# controller.net
KiCad netlist of a schematic drawn in Altium Designer
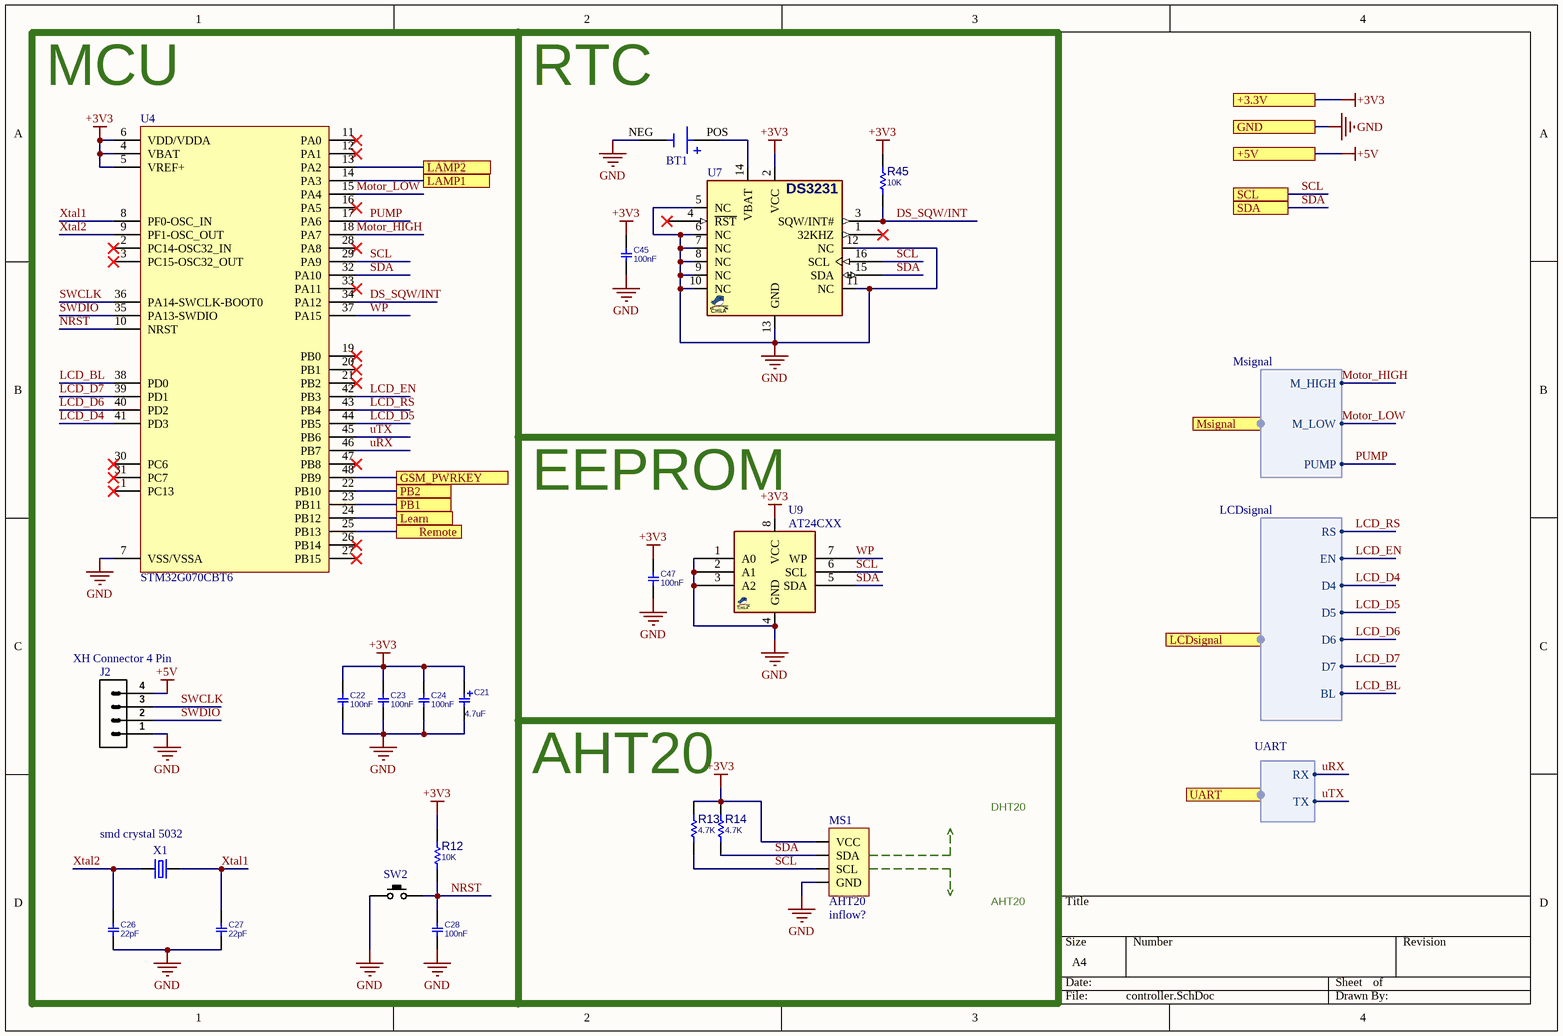
[diagram p0: controller.SchDoc]

(export (version "E")
  (design (tool "Eeschema 10.0.6"))
  (components
    (comp (ref "BT1")
      (value "Coin Cell battery holder")
      (footprint "Coin Cell battery holder")
      (description "2032 Battery")
      (libsource (lib "Mehrdad") (part "Coin Cell battery holder"))
    )
    (comp (ref "C21")
      (value "4.7uF")
      (footprint "C_TN_3216")
      (description "CAP, SMD, TAN,")
      (libsource (lib "passive_smd") (part "CAP_SMD_TAN"))
    )
    (comp (ref "C22")
      (value "100nF")
      (footprint "C0805")
      (description "CAP, MLCC, -F, -V, MATERIAL, -%, 0201")
      (fields (field (name "MANF_P#") "MANF_PART#"))
      (libsource (lib "passive_smd") (part "CAP_SMD_MLCC_0805"))
    )
    (comp (ref "C23")
      (value "100nF")
      (footprint "C0805")
      (description "CAP, MLCC, -F, -V, MATERIAL, -%, 0201")
      (fields (field (name "MANF_P#") "MANF_PART#"))
      (libsource (lib "passive_smd") (part "CAP_SMD_MLCC_0805"))
    )
    (comp (ref "C24")
      (value "100nF")
      (footprint "C0805")
      (description "CAP, MLCC, -F, -V, MATERIAL, -%, 0201")
      (fields (field (name "MANF_P#") "MANF_PART#"))
      (libsource (lib "passive_smd") (part "CAP_SMD_MLCC_0805"))
    )
    (comp (ref "C26")
      (value "22pF")
      (footprint "C0805")
      (description "CAP, MLCC, -F, -V, MATERIAL, -%, 0201")
      (fields (field (name "MANF_P#") "MANF_PART#"))
      (libsource (lib "passive_smd") (part "CAP_SMD_MLCC_0805"))
    )
    (comp (ref "C27")
      (value "22pF")
      (footprint "C0805")
      (description "CAP, MLCC, -F, -V, MATERIAL, -%, 0201")
      (fields (field (name "MANF_P#") "MANF_PART#"))
      (libsource (lib "passive_smd") (part "CAP_SMD_MLCC_0805"))
    )
    (comp (ref "C28")
      (value "100nF")
      (footprint "C0805")
      (description "CAP, MLCC, -F, -V, MATERIAL, -%, 0201")
      (fields (field (name "MANF_P#") "MANF_PART#"))
      (libsource (lib "passive_smd") (part "CAP_SMD_MLCC_0805"))
    )
    (comp (ref "C45")
      (value "100nF")
      (footprint "C0805")
      (description "CAP, MLCC, -F, -V, MATERIAL, -%, 0201")
      (fields (field (name "MANF_P#") "MANF_PART#"))
      (libsource (lib "passive_smd") (part "CAP_SMD_MLCC_0805"))
    )
    (comp (ref "C47")
      (value "100nF")
      (footprint "C0805")
      (description "CAP, MLCC, -F, -V, MATERIAL, -%, 0201")
      (fields (field (name "MANF_P#") "MANF_PART#"))
      (libsource (lib "passive_smd") (part "CAP_SMD_MLCC_0805"))
    )
    (comp (ref "J2")
      (value "XH Connector 4 Pin")
      (footprint "XH 4 Pin - 2.5mm")
      (description "XH, 4-Pin")
      (fields (field (name "PUBLISHER") "Majid Derhambakhsh"))
      (libsource (lib "mBedLab Altium Library (2024-04-20)") (part "XH 4"))
    )
    (comp (ref "MS1")
      (value "AHT20")
      (footprint "AHT20")
      (description "Air Temperature and Humidity Sensor")
      (fields (field (name "INFLOW") "inflow?") (field (name "VALIDATION") "NT"))
      (libsource (lib "AVR_RCS") (part "ModSen_AHT20"))
    )
    (comp (ref "R12")
      (value "10K")
      (footprint "R0805")
      (description "RESISTOR, SMD")
      (libsource (lib "passive_smd") (part "RES_SMD_0805"))
    )
    (comp (ref "R13")
      (value "4.7K")
      (footprint "R0805")
      (description "RESISTOR, SMD")
      (libsource (lib "passive_smd") (part "RES_SMD_0805"))
    )
    (comp (ref "R14")
      (value "4.7K")
      (footprint "R0805")
      (description "RESISTOR, SMD")
      (libsource (lib "passive_smd") (part "RES_SMD_0805"))
    )
    (comp (ref "R45")
      (value "10K")
      (footprint "R0805")
      (description "RESISTOR, SMD")
      (libsource (lib "passive_smd") (part "RES_SMD_0805"))
    )
    (comp (ref "SW2")
      (value "Tactile Switch")
      (footprint "Tactile Switch")
      (description "3x6x5 mm - 2 Pin")
      (libsource (lib "Mehrdad") (part "Tactile Switch"))
    )
    (comp (ref "U4")
      (value "STM32G070CBT6")
      (footprint "STM32G070CBT6")
      (description "ARMÂ® CortexÂ®-M0+ STM32G0 Microcontroller IC 32-Bit 64MHz 128KB _128K x 8_ FLASH 48-LQFP _7x7_")
      (libsource (lib "Mehrdad") (part "STM32G070CBT6"))
    )
    (comp (ref "U7")
      (value "DS3231")
      (footprint "SO_16_W")
      (description "Real-Time Clock, I2C, +IntCryst")
      (fields (field (name "MANF") "Maxim Integrated") (field (name "MANF_P#") "DS3231SN#"))
      (libsource (lib "rtc") (part "DS3231_SOP16W"))
    )
    (comp (ref "U9")
      (value "AT24CXX")
      (footprint "SO_8")
      (description "EEPROM, I2C,")
      (libsource (lib "memory_eeprom_I2C") (part "EEPROM_I2C_AT24CXX_SOP8"))
    )
    (comp (ref "X1")
      (value "smd crystal 5032")
      (footprint "smd crystal 5032")
      (description "8Mhz - 2Pin - 5032 Package")
      (libsource (lib "Mehrdad") (part "smd crystal 5032"))
    )
  )
  (nets
    (net (code "4") (name "+3V3") (class "Default")
      (node (ref "C21") (pin "1") (pinfunction "1_1") (pintype "passive"))
      (node (ref "C22") (pin "2") (pinfunction "2_2") (pintype "passive"))
      (node (ref "C23") (pin "2") (pinfunction "2_2") (pintype "passive"))
      (node (ref "C24") (pin "2") (pinfunction "2_2") (pintype "passive"))
      (node (ref "C45") (pin "2") (pinfunction "2_2") (pintype "passive"))
      (node (ref "C47") (pin "2") (pinfunction "2_2") (pintype "passive"))
      (node (ref "MS1") (pin "4") (pinfunction "VCC_4") (pintype "passive"))
      (node (ref "R12") (pin "1") (pinfunction "1_1") (pintype "passive"))
      (node (ref "R13") (pin "1") (pinfunction "1_1") (pintype "passive"))
      (node (ref "R14") (pin "1") (pinfunction "1_1") (pintype "passive"))
      (node (ref "R45") (pin "1") (pinfunction "1_1") (pintype "passive"))
      (node (ref "U4") (pin "4") (pinfunction "VBAT_4") (pintype "power_in"))
      (node (ref "U4") (pin "5") (pinfunction "VREF+_5") (pintype "power_in"))
      (node (ref "U4") (pin "6") (pinfunction "VDD/VDDA_6") (pintype "power_in"))
      (node (ref "U7") (pin "2") (pinfunction "VCC_2") (pintype "power_in"))
      (node (ref "U9") (pin "8") (pinfunction "VCC_8") (pintype "passive"))
    )
    (net (code "5") (name "+5V") (class "Default")
      (node (ref "J2") (pin "4") (pinfunction "4_4") (pintype "passive"))
    )
    (net (code "6") (name "/DS_SQW{slash}INT") (class "Default")
      (node (ref "R45") (pin "2") (pinfunction "2_2") (pintype "passive"))
      (node (ref "U4") (pin "34") (pinfunction "PA12_34") (pintype "power_in"))
      (node (ref "U7") (pin "3") (pinfunction "SQW/INT#_3") (pintype "output"))
    )
    (net (code "7") (name "/GSM_PWRKEY") (class "Default")
      (node (ref "U4") (pin "48") (pinfunction "PB9_48") (pintype "power_in"))
    )
    (net (code "8") (name "/LAMP1") (class "Default")
      (node (ref "U4") (pin "14") (pinfunction "PA3_14") (pintype "power_in"))
    )
    (net (code "9") (name "/LAMP2") (class "Default")
      (node (ref "U4") (pin "13") (pinfunction "PA2_13") (pintype "power_in"))
    )
    (net (code "10") (name "/LCD_BL") (class "Default")
      (node (ref "U4") (pin "38") (pinfunction "PD0_38") (pintype "power_in"))
    )
    (net (code "11") (name "/LCD_D4") (class "Default")
      (node (ref "U4") (pin "41") (pinfunction "PD3_41") (pintype "power_in"))
    )
    (net (code "12") (name "/LCD_D5") (class "Default")
      (node (ref "U4") (pin "44") (pinfunction "PB5_44") (pintype "power_in"))
    )
    (net (code "13") (name "/LCD_D6") (class "Default")
      (node (ref "U4") (pin "40") (pinfunction "PD2_40") (pintype "power_in"))
    )
    (net (code "14") (name "/LCD_D7") (class "Default")
      (node (ref "U4") (pin "39") (pinfunction "PD1_39") (pintype "power_in"))
    )
    (net (code "15") (name "/LCD_EN") (class "Default")
      (node (ref "U4") (pin "42") (pinfunction "PB3_42") (pintype "power_in"))
    )
    (net (code "16") (name "/LCD_RS") (class "Default")
      (node (ref "U4") (pin "43") (pinfunction "PB4_43") (pintype "power_in"))
    )
    (net (code "17") (name "/Learn") (class "Default")
      (node (ref "U4") (pin "24") (pinfunction "PB12_24") (pintype "power_in"))
    )
    (net (code "18") (name "/Motor_HIGH") (class "Default")
      (node (ref "U4") (pin "18") (pinfunction "PA7_18") (pintype "power_in"))
    )
    (net (code "19") (name "/Motor_LOW") (class "Default")
      (node (ref "U4") (pin "15") (pinfunction "PA4_15") (pintype "power_in"))
    )
    (net (code "20") (name "/NRST") (class "Default")
      (node (ref "C28") (pin "2") (pinfunction "2_2") (pintype "passive"))
      (node (ref "R12") (pin "2") (pinfunction "2_2") (pintype "passive"))
      (node (ref "SW2") (pin "2") (pinfunction "P3_2") (pintype "passive"))
      (node (ref "U4") (pin "10") (pinfunction "NRST_10") (pintype "power_in"))
    )
    (net (code "21") (name "/PB1") (class "Default")
      (node (ref "U4") (pin "23") (pinfunction "PB11_23") (pintype "power_in"))
    )
    (net (code "22") (name "/PB2") (class "Default")
      (node (ref "U4") (pin "22") (pinfunction "PB10_22") (pintype "power_in"))
    )
    (net (code "23") (name "/PUMP") (class "Default")
      (node (ref "U4") (pin "17") (pinfunction "PA6_17") (pintype "power_in"))
    )
    (net (code "24") (name "/Remote") (class "Default")
      (node (ref "U4") (pin "25") (pinfunction "PB13_25") (pintype "power_in"))
    )
    (net (code "25") (name "/SCL") (class "Default")
      (node (ref "MS1") (pin "2") (pinfunction "SCL_2") (pintype "passive"))
      (node (ref "R13") (pin "2") (pinfunction "2_2") (pintype "passive"))
      (node (ref "U4") (pin "29") (pinfunction "PA9_29") (pintype "power_in"))
      (node (ref "U7") (pin "16") (pinfunction "SCL_16") (pintype "input"))
      (node (ref "U9") (pin "6") (pinfunction "SCL_6") (pintype "passive"))
    )
    (net (code "26") (name "/SDA") (class "Default")
      (node (ref "MS1") (pin "1") (pinfunction "SDA_1") (pintype "passive"))
      (node (ref "R14") (pin "2") (pinfunction "2_2") (pintype "passive"))
      (node (ref "U4") (pin "32") (pinfunction "PA10_32") (pintype "power_in"))
      (node (ref "U7") (pin "15") (pinfunction "SDA_15") (pintype "bidirectional"))
      (node (ref "U9") (pin "5") (pinfunction "SDA_5") (pintype "passive"))
    )
    (net (code "27") (name "/SWCLK") (class "Default")
      (node (ref "J2") (pin "3") (pinfunction "3_3") (pintype "passive"))
      (node (ref "U4") (pin "36") (pinfunction "PA14-SWCLK-BOOT0_36") (pintype "power_in"))
    )
    (net (code "28") (name "/SWDIO") (class "Default")
      (node (ref "J2") (pin "2") (pinfunction "2_2") (pintype "passive"))
      (node (ref "U4") (pin "35") (pinfunction "PA13-SWDIO_35") (pintype "power_in"))
    )
    (net (code "29") (name "/WP") (class "Default")
      (node (ref "U4") (pin "37") (pinfunction "PA15_37") (pintype "power_in"))
      (node (ref "U9") (pin "7") (pinfunction "WP_7") (pintype "passive"))
    )
    (net (code "30") (name "/Xtal1") (class "Default")
      (node (ref "C27") (pin "1") (pinfunction "1_1") (pintype "passive"))
      (node (ref "U4") (pin "8") (pinfunction "PF0-OSC_IN_8") (pintype "power_in"))
      (node (ref "X1") (pin "2") (pinfunction "2_2") (pintype "passive"))
    )
    (net (code "31") (name "/Xtal2") (class "Default")
      (node (ref "C26") (pin "1") (pinfunction "1_1") (pintype "passive"))
      (node (ref "U4") (pin "9") (pinfunction "PF1-OSC_OUT_9") (pintype "power_in"))
      (node (ref "X1") (pin "1") (pinfunction "1_1") (pintype "passive"))
    )
    (net (code "32") (name "/uRX") (class "Default")
      (node (ref "U4") (pin "46") (pinfunction "PB7_46") (pintype "power_in"))
    )
    (net (code "33") (name "/uTX") (class "Default")
      (node (ref "U4") (pin "45") (pinfunction "PB6_45") (pintype "power_in"))
    )
    (net (code "37") (name "GND") (class "Default")
      (node (ref "BT1") (pin "NEG") (pinfunction "NEG_NEG") (pintype "passive"))
      (node (ref "C21") (pin "2") (pinfunction "2_2") (pintype "passive"))
      (node (ref "C22") (pin "1") (pinfunction "1_1") (pintype "passive"))
      (node (ref "C23") (pin "1") (pinfunction "1_1") (pintype "passive"))
      (node (ref "C24") (pin "1") (pinfunction "1_1") (pintype "passive"))
      (node (ref "C26") (pin "2") (pinfunction "2_2") (pintype "passive"))
      (node (ref "C27") (pin "2") (pinfunction "2_2") (pintype "passive"))
      (node (ref "C28") (pin "1") (pinfunction "1_1") (pintype "passive"))
      (node (ref "C45") (pin "1") (pinfunction "1_1") (pintype "passive"))
      (node (ref "C47") (pin "1") (pinfunction "1_1") (pintype "passive"))
      (node (ref "J2") (pin "1") (pinfunction "1_1") (pintype "passive"))
      (node (ref "MS1") (pin "3") (pinfunction "GND_3") (pintype "passive"))
      (node (ref "SW2") (pin "1") (pinfunction "P1_1") (pintype "passive"))
      (node (ref "U4") (pin "7") (pinfunction "VSS/VSSA_7") (pintype "power_in"))
      (node (ref "U7") (pin "10") (pinfunction "NC_10") (pintype "passive"))
      (node (ref "U7") (pin "11") (pinfunction "NC_11") (pintype "passive"))
      (node (ref "U7") (pin "12") (pinfunction "NC_12") (pintype "passive"))
      (node (ref "U7") (pin "13") (pinfunction "GND_13") (pintype "power_in"))
      (node (ref "U7") (pin "5") (pinfunction "NC_5") (pintype "passive"))
      (node (ref "U7") (pin "6") (pinfunction "NC_6") (pintype "passive"))
      (node (ref "U7") (pin "7") (pinfunction "NC_7") (pintype "passive"))
      (node (ref "U7") (pin "8") (pinfunction "NC_8") (pintype "passive"))
      (node (ref "U7") (pin "9") (pinfunction "NC_9") (pintype "passive"))
      (node (ref "U9") (pin "1") (pinfunction "A0_1") (pintype "passive"))
      (node (ref "U9") (pin "2") (pinfunction "A1_2") (pintype "passive"))
      (node (ref "U9") (pin "3") (pinfunction "A2_3") (pintype "passive"))
      (node (ref "U9") (pin "4") (pinfunction "GND_4") (pintype "passive"))
    )
    (net (code "38") (name "Net-(U7-VBAT)") (class "Default")
      (node (ref "BT1") (pin "POS") (pinfunction "POS_POS") (pintype "passive"))
      (node (ref "U7") (pin "14") (pinfunction "VBAT_14") (pintype "power_in"))
    )
    (net (code "39") (name "unconnected-(U4-PA0-Pad11)") (class "Default")
      (node (ref "U4") (pin "11") (pinfunction "PA0_11") (pintype "power_in+no_connect"))
    )
    (net (code "40") (name "unconnected-(U4-PA1-Pad12)") (class "Default")
      (node (ref "U4") (pin "12") (pinfunction "PA1_12") (pintype "power_in+no_connect"))
    )
    (net (code "41") (name "unconnected-(U4-PA5-Pad16)") (class "Default")
      (node (ref "U4") (pin "16") (pinfunction "PA5_16") (pintype "power_in+no_connect"))
    )
    (net (code "42") (name "unconnected-(U4-PA8-Pad28)") (class "Default")
      (node (ref "U4") (pin "28") (pinfunction "PA8_28") (pintype "power_in+no_connect"))
    )
    (net (code "43") (name "unconnected-(U4-PA11-Pad33)") (class "Default")
      (node (ref "U4") (pin "33") (pinfunction "PA11_33") (pintype "power_in+no_connect"))
    )
    (net (code "44") (name "unconnected-(U4-PB0-Pad19)") (class "Default")
      (node (ref "U4") (pin "19") (pinfunction "PB0_19") (pintype "power_in+no_connect"))
    )
    (net (code "45") (name "unconnected-(U4-PB1-Pad20)") (class "Default")
      (node (ref "U4") (pin "20") (pinfunction "PB1_20") (pintype "power_in+no_connect"))
    )
    (net (code "46") (name "unconnected-(U4-PB2-Pad21)") (class "Default")
      (node (ref "U4") (pin "21") (pinfunction "PB2_21") (pintype "power_in+no_connect"))
    )
    (net (code "47") (name "unconnected-(U4-PB8-Pad47)") (class "Default")
      (node (ref "U4") (pin "47") (pinfunction "PB8_47") (pintype "power_in+no_connect"))
    )
    (net (code "48") (name "unconnected-(U4-PB14-Pad26)") (class "Default")
      (node (ref "U4") (pin "26") (pinfunction "PB14_26") (pintype "power_in+no_connect"))
    )
    (net (code "49") (name "unconnected-(U4-PB15-Pad27)") (class "Default")
      (node (ref "U4") (pin "27") (pinfunction "PB15_27") (pintype "power_in+no_connect"))
    )
    (net (code "50") (name "unconnected-(U4-PC6-Pad30)") (class "Default")
      (node (ref "U4") (pin "30") (pinfunction "PC6_30") (pintype "power_in+no_connect"))
    )
    (net (code "51") (name "unconnected-(U4-PC7-Pad31)") (class "Default")
      (node (ref "U4") (pin "31") (pinfunction "PC7_31") (pintype "power_in+no_connect"))
    )
    (net (code "52") (name "unconnected-(U4-PC13-Pad1)") (class "Default")
      (node (ref "U4") (pin "1") (pinfunction "PC13_1") (pintype "power_in+no_connect"))
    )
    (net (code "53") (name "unconnected-(U4-PC14-OSC32_IN-Pad2)") (class "Default")
      (node (ref "U4") (pin "2") (pinfunction "PC14-OSC32_IN_2") (pintype "power_in+no_connect"))
    )
    (net (code "54") (name "unconnected-(U4-PC15-OSC32_OUT-Pad3)") (class "Default")
      (node (ref "U4") (pin "3") (pinfunction "PC15-OSC32_OUT_3") (pintype "power_in+no_connect"))
    )
    (net (code "55") (name "unconnected-(U7-32KHZ-Pad1)") (class "Default")
      (node (ref "U7") (pin "1") (pinfunction "32KHZ_1") (pintype "output+no_connect"))
    )
    (net (code "56") (name "unconnected-(U7-~{RST}-Pad4)") (class "Default")
      (node (ref "U7") (pin "4") (pinfunction "~{RST}_4") (pintype "input+no_connect"))
    )
  )
)
